# Constant_current.net
KiCad netlist of a schematic drawn in EAGLE
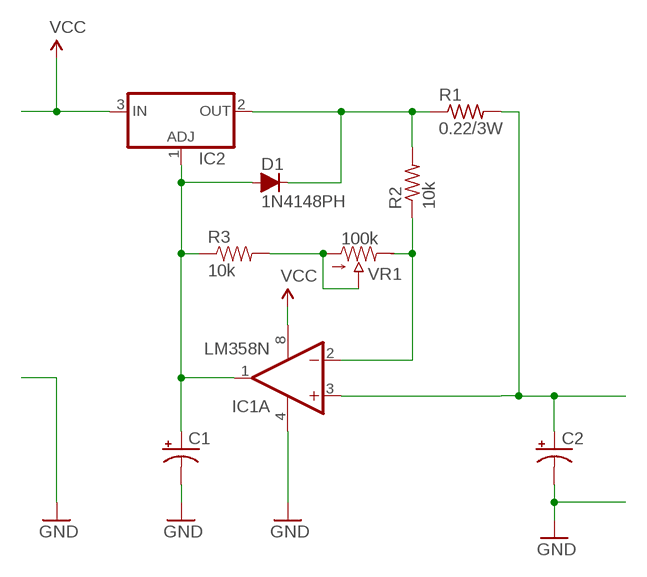
[diagram p0: schematic, sheet 1]

(export (version "E")
  (design (tool "Eeschema 10.0.6"))
  (components
    (comp (ref "C1")
      (value "CAP_POLPTH1")
      (footprint "eagle-import:CPOL-RADIAL-100UF-25V")
      (libsource (lib "eagle-import") (part "CAP_POLPTH1"))
    )
    (comp (ref "C2")
      (value "CAP_POLPTH1")
      (footprint "eagle-import:CPOL-RADIAL-100UF-25V")
      (libsource (lib "eagle-import") (part "CAP_POLPTH1"))
    )
    (comp (ref "D1")
      (value "1N4148PH")
      (footprint "eagle-import:DO35-7")
      (libsource (lib "eagle-import") (part "1N4148PH"))
    )
    (comp (ref "IC1")
      (value "LM358N")
      (footprint "eagle-import:DIL08")
      (libsource (lib "eagle-import") (part "LM358N"))
    )
    (comp (ref "IC2")
      (value "LM338T")
      (footprint "eagle-import:TO220V-REG")
      (libsource (lib "eagle-import") (part "LM338T"))
    )
    (comp (ref "R1")
      (value "0.22/3W")
      (footprint "eagle-import:0414_15")
      (libsource (lib "eagle-import") (part "R-US_0414/15"))
    )
    (comp (ref "R2")
      (value "10k")
      (footprint "eagle-import:0414_15")
      (libsource (lib "eagle-import") (part "R-US_0414/15"))
    )
    (comp (ref "R3")
      (value "10k")
      (footprint "eagle-import:AXIAL-0.3-KIT")
      (libsource (lib "eagle-import") (part "RESISTORKIT"))
    )
    (comp (ref "VR1")
      (value "100k")
      (footprint "eagle-import:3362U")
      (libsource (lib "eagle-import") (part "POT100K_3362U"))
    )
  )
  (nets
    (net (code "1") (name "GND") (class "Default")
      (node (ref "C1") (pin "2") (pinfunction "-_2") (pintype "passive"))
      (node (ref "C2") (pin "2") (pinfunction "-_2") (pintype "passive"))
      (node (ref "IC1") (pin "4") (pinfunction "V-_4") (pintype "power_in"))
    )
    (net (code "2") (name "Net-(C1-+)") (class "Default")
      (node (ref "C1") (pin "1") (pinfunction "+_1") (pintype "passive"))
      (node (ref "D1") (pin "A") (pinfunction "A_A") (pintype "passive"))
      (node (ref "IC1") (pin "1") (pinfunction "OUT_1") (pintype "output"))
      (node (ref "IC2") (pin "1") (pinfunction "ADJ_1") (pintype "input"))
      (node (ref "R3") (pin "P$1") (pinfunction "1_P$1") (pintype "passive"))
    )
    (net (code "3") (name "Net-(C2-+)") (class "Default")
      (node (ref "C2") (pin "1") (pinfunction "+_1") (pintype "passive"))
      (node (ref "IC1") (pin "3") (pinfunction "+IN_3") (pintype "input"))
      (node (ref "R1") (pin "2") (pinfunction "2_2") (pintype "passive"))
    )
    (net (code "4") (name "Net-(IC1A--IN)") (class "Default")
      (node (ref "IC1") (pin "2") (pinfunction "-IN_2") (pintype "input"))
      (node (ref "R2") (pin "1") (pinfunction "1_1") (pintype "passive"))
      (node (ref "VR1") (pin "P$1") (pinfunction "E_P$1") (pintype "passive"))
    )
    (net (code "5") (name "Net-(IC2-OUT)") (class "Default")
      (node (ref "D1") (pin "C") (pinfunction "C_C") (pintype "passive"))
      (node (ref "IC2") (pin "2") (pinfunction "OUT_2") (pintype "passive"))
      (node (ref "R1") (pin "1") (pinfunction "1_1") (pintype "passive"))
      (node (ref "R2") (pin "2") (pinfunction "2_2") (pintype "passive"))
    )
    (net (code "6") (name "Net-(R3-2)") (class "Default")
      (node (ref "R3") (pin "P$2") (pinfunction "2_P$2") (pintype "passive"))
      (node (ref "VR1") (pin "P$2") (pinfunction "S_P$2") (pintype "passive"))
      (node (ref "VR1") (pin "P$3") (pinfunction "A_P$3") (pintype "passive"))
    )
    (net (code "7") (name "VCC") (class "Default")
      (node (ref "IC1") (pin "8") (pinfunction "V+_8") (pintype "power_in"))
      (node (ref "IC2") (pin "3") (pinfunction "IN_3") (pintype "input"))
    )
  )
)
